# ospiLCD.net
KiCad netlist of a schematic drawn in EAGLE
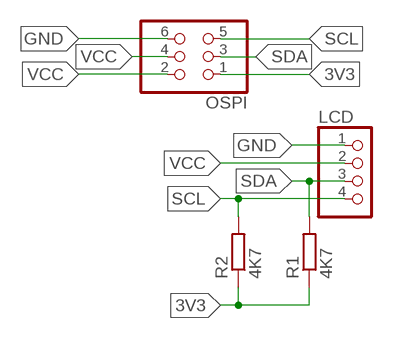
[diagram p0: schematic, sheet 1]

(export (version "E")
  (design (tool "Eeschema 10.0.6"))
  (components
    (comp (ref "LCD")
      (value "PINHD-1X4")
      (footprint "eagle-import:1X04")
      (libsource (lib "eagle-import") (part "PINHD-1X4"))
    )
    (comp (ref "OSPI")
      (value "PINHD-2X3")
      (footprint "eagle-import:2X03")
      (libsource (lib "eagle-import") (part "PINHD-2X3"))
    )
    (comp (ref "R1")
      (value "4K7")
      (footprint "eagle-import:R0603")
      (libsource (lib "eagle-import") (part "R-EU_R0603"))
    )
    (comp (ref "R2")
      (value "4K7")
      (footprint "eagle-import:R0603")
      (libsource (lib "eagle-import") (part "R-EU_R0603"))
    )
  )
  (nets
    (net (code "1") (name "3V3") (class "Default")
      (node (ref "OSPI") (pin "1") (pinfunction "1_1") (pintype "passive"))
      (node (ref "R1") (pin "1") (pinfunction "1_1") (pintype "passive"))
      (node (ref "R2") (pin "1") (pinfunction "1_1") (pintype "passive"))
    )
    (net (code "2") (name "GND") (class "Default")
      (node (ref "LCD") (pin "1") (pinfunction "1_1") (pintype "passive"))
      (node (ref "OSPI") (pin "6") (pinfunction "6_6") (pintype "passive"))
    )
    (net (code "3") (name "SCL") (class "Default")
      (node (ref "LCD") (pin "4") (pinfunction "4_4") (pintype "passive"))
      (node (ref "OSPI") (pin "5") (pinfunction "5_5") (pintype "passive"))
      (node (ref "R2") (pin "2") (pinfunction "2_2") (pintype "passive"))
    )
    (net (code "4") (name "SDA") (class "Default")
      (node (ref "LCD") (pin "3") (pinfunction "3_3") (pintype "passive"))
      (node (ref "OSPI") (pin "3") (pinfunction "3_3") (pintype "passive"))
      (node (ref "R1") (pin "2") (pinfunction "2_2") (pintype "passive"))
    )
    (net (code "5") (name "VCC") (class "Default")
      (node (ref "LCD") (pin "2") (pinfunction "2_2") (pintype "passive"))
      (node (ref "OSPI") (pin "2") (pinfunction "2_2") (pintype "passive"))
      (node (ref "OSPI") (pin "4") (pinfunction "4_4") (pintype "passive"))
    )
  )
)
